# tricorder-photodiode-breakout-mk-1_1.net
KiCad netlist of a schematic drawn in EAGLE
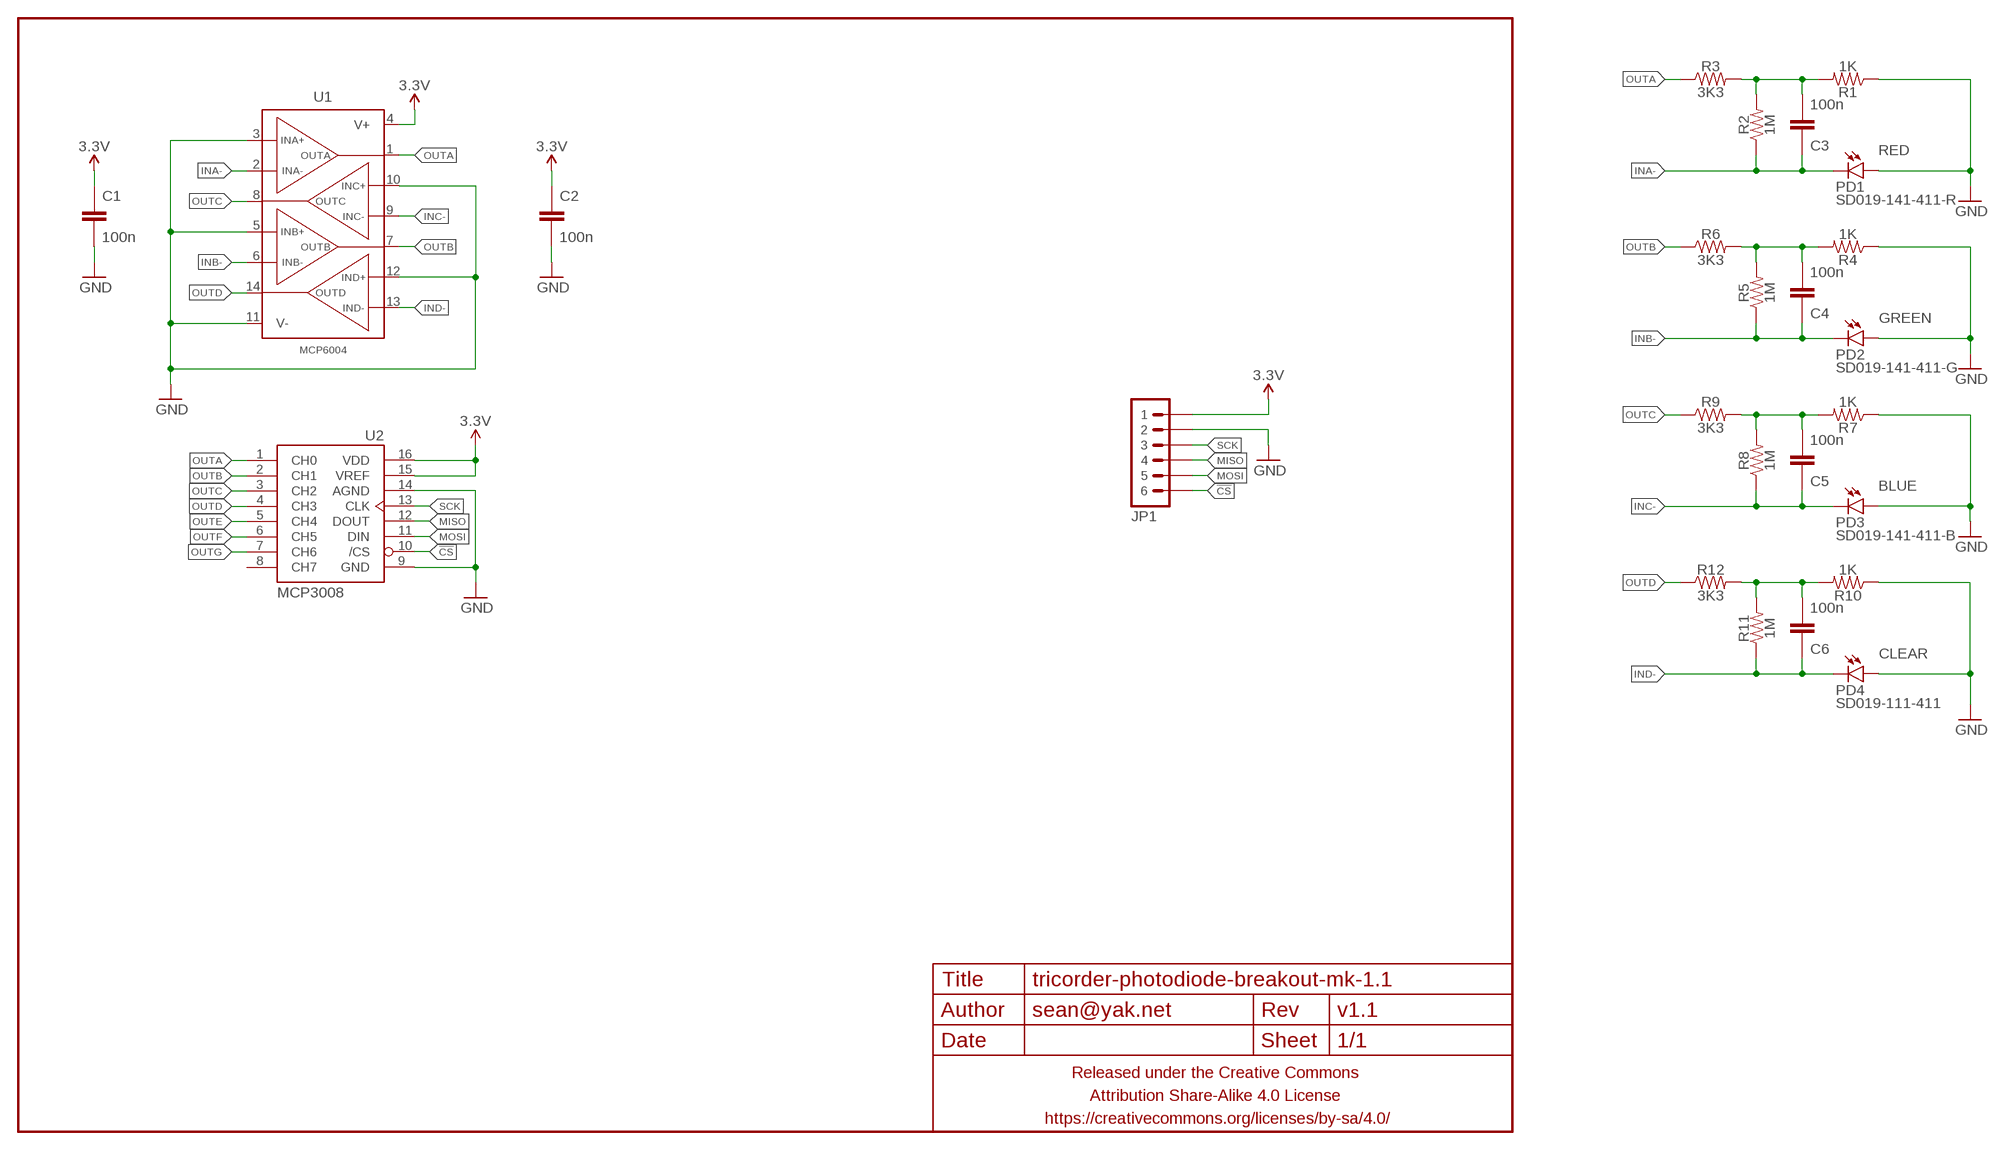
[diagram p0: schematic, sheet 1]

(export (version "E")
  (design (tool "Eeschema 10.0.6"))
  (components
    (comp (ref "C1")
      (value "100n")
      (footprint "eagle-import:C0603")
      (libsource (lib "eagle-import") (part "CAPACITOR-CERAMICC0603"))
    )
    (comp (ref "C2")
      (value "100n")
      (footprint "eagle-import:C0603")
      (libsource (lib "eagle-import") (part "CAPACITOR-CERAMICC0603"))
    )
    (comp (ref "C3")
      (value "100n")
      (footprint "eagle-import:C0603")
      (libsource (lib "eagle-import") (part "CAPACITOR-CERAMICC0603"))
    )
    (comp (ref "C4")
      (value "100n")
      (footprint "eagle-import:C0603")
      (libsource (lib "eagle-import") (part "CAPACITOR-CERAMICC0603"))
    )
    (comp (ref "C5")
      (value "100n")
      (footprint "eagle-import:C0603")
      (libsource (lib "eagle-import") (part "CAPACITOR-CERAMICC0603"))
    )
    (comp (ref "C6")
      (value "100n")
      (footprint "eagle-import:C0603")
      (libsource (lib "eagle-import") (part "CAPACITOR-CERAMICC0603"))
    )
    (comp (ref "FRAME1")
      (value "FRAME-LETTERNO_PACKAGE")
      (footprint "eagle-import:DUMMY")
      (fields (field (name "DESIGNER") "sean@yak.net") (field (name "VERSION") "v1.1"))
      (libsource (lib "eagle-import") (part "FRAME-LETTERNO_PACKAGE"))
    )
    (comp (ref "JP1")
      (value "M06JST-PH-PTH-VERT")
      (footprint "eagle-import:JST-6-PH-VERT-PTH")
      (libsource (lib "eagle-import") (part "M06JST-PH-PTH-VERT"))
    )
    (comp (ref "PD1")
      (value "SD019-141-411-R")
      (footprint "eagle-import:LED-0805")
      (libsource (lib "eagle-import") (part "PHOTODIODESMD-0805"))
    )
    (comp (ref "PD2")
      (value "SD019-141-411-G")
      (footprint "eagle-import:LED-0805")
      (libsource (lib "eagle-import") (part "PHOTODIODESMD-0805"))
    )
    (comp (ref "PD3")
      (value "SD019-141-411-B")
      (footprint "eagle-import:LED-0805")
      (libsource (lib "eagle-import") (part "PHOTODIODESMD-0805"))
    )
    (comp (ref "PD4")
      (value "SD019-111-411")
      (footprint "eagle-import:LED-0805")
      (libsource (lib "eagle-import") (part "PHOTODIODESMD-0805"))
    )
    (comp (ref "R1")
      (value "1K")
      (footprint "eagle-import:R0603")
      (libsource (lib "eagle-import") (part "RESISTORR0603"))
    )
    (comp (ref "R2")
      (value "1M")
      (footprint "eagle-import:R0603")
      (libsource (lib "eagle-import") (part "RESISTORR0603"))
    )
    (comp (ref "R3")
      (value "3K3")
      (footprint "eagle-import:R0603")
      (libsource (lib "eagle-import") (part "RESISTORR0603"))
    )
    (comp (ref "R4")
      (value "1K")
      (footprint "eagle-import:R0603")
      (libsource (lib "eagle-import") (part "RESISTORR0603"))
    )
    (comp (ref "R5")
      (value "1M")
      (footprint "eagle-import:R0603")
      (libsource (lib "eagle-import") (part "RESISTORR0603"))
    )
    (comp (ref "R6")
      (value "3K3")
      (footprint "eagle-import:R0603")
      (libsource (lib "eagle-import") (part "RESISTORR0603"))
    )
    (comp (ref "R7")
      (value "1K")
      (footprint "eagle-import:R0603")
      (libsource (lib "eagle-import") (part "RESISTORR0603"))
    )
    (comp (ref "R8")
      (value "1M")
      (footprint "eagle-import:R0603")
      (libsource (lib "eagle-import") (part "RESISTORR0603"))
    )
    (comp (ref "R9")
      (value "3K3")
      (footprint "eagle-import:R0603")
      (libsource (lib "eagle-import") (part "RESISTORR0603"))
    )
    (comp (ref "R10")
      (value "1K")
      (footprint "eagle-import:R0603")
      (libsource (lib "eagle-import") (part "RESISTORR0603"))
    )
    (comp (ref "R11")
      (value "1M")
      (footprint "eagle-import:R0603")
      (libsource (lib "eagle-import") (part "RESISTORR0603"))
    )
    (comp (ref "R12")
      (value "3K3")
      (footprint "eagle-import:R0603")
      (libsource (lib "eagle-import") (part "RESISTORR0603"))
    )
    (comp (ref "U1")
      (value "MCP6004")
      (footprint "eagle-import:SO14")
      (libsource (lib "eagle-import") (part "MCP6004SOIC14"))
    )
    (comp (ref "U2")
      (value "MCP3008")
      (footprint "eagle-import:SO16")
      (libsource (lib "eagle-import") (part "MCP3008SOIC16"))
    )
  )
  (nets
    (net (code "1") (name "/~{CS}") (class "Default")
      (node (ref "JP1") (pin "6") (pinfunction "6_6") (pintype "passive"))
      (node (ref "U2") (pin "10") (pinfunction "/CS_10") (pintype "input"))
    )
    (net (code "2") (name "3.3V") (class "Default")
      (node (ref "C1") (pin "1") (pinfunction "1_1") (pintype "passive"))
      (node (ref "C2") (pin "1") (pinfunction "1_1") (pintype "passive"))
      (node (ref "JP1") (pin "1") (pinfunction "1_1") (pintype "passive"))
      (node (ref "U1") (pin "4") (pinfunction "V+_4") (pintype "power_in"))
      (node (ref "U2") (pin "15") (pinfunction "VREF_15") (pintype "input"))
      (node (ref "U2") (pin "16") (pinfunction "VDD_16") (pintype "power_in"))
    )
    (net (code "3") (name "GND") (class "Default")
      (node (ref "C1") (pin "2") (pinfunction "2_2") (pintype "passive"))
      (node (ref "C2") (pin "2") (pinfunction "2_2") (pintype "passive"))
      (node (ref "JP1") (pin "2") (pinfunction "2_2") (pintype "passive"))
      (node (ref "PD1") (pin "A") (pinfunction "A_A") (pintype "passive"))
      (node (ref "PD2") (pin "A") (pinfunction "A_A") (pintype "passive"))
      (node (ref "PD3") (pin "A") (pinfunction "A_A") (pintype "passive"))
      (node (ref "PD4") (pin "A") (pinfunction "A_A") (pintype "passive"))
      (node (ref "R1") (pin "1") (pinfunction "1_1") (pintype "passive"))
      (node (ref "R10") (pin "1") (pinfunction "1_1") (pintype "passive"))
      (node (ref "R4") (pin "1") (pinfunction "1_1") (pintype "passive"))
      (node (ref "R7") (pin "1") (pinfunction "1_1") (pintype "passive"))
      (node (ref "U1") (pin "10") (pinfunction "INC+_10") (pintype "input"))
      (node (ref "U1") (pin "11") (pinfunction "V-_11") (pintype "power_in"))
      (node (ref "U1") (pin "12") (pinfunction "IND+_12") (pintype "input"))
      (node (ref "U1") (pin "3") (pinfunction "INA+_3") (pintype "input"))
      (node (ref "U1") (pin "5") (pinfunction "INB+_5") (pintype "input"))
      (node (ref "U2") (pin "14") (pinfunction "AGND_14") (pintype "power_in"))
      (node (ref "U2") (pin "9") (pinfunction "GND_9") (pintype "power_in"))
    )
    (net (code "4") (name "INA-") (class "Default")
      (node (ref "C3") (pin "1") (pinfunction "1_1") (pintype "passive"))
      (node (ref "PD1") (pin "C") (pinfunction "C_C") (pintype "passive"))
      (node (ref "R2") (pin "1") (pinfunction "1_1") (pintype "passive"))
      (node (ref "U1") (pin "2") (pinfunction "INA-_2") (pintype "input"))
    )
    (net (code "5") (name "INB-") (class "Default")
      (node (ref "C4") (pin "1") (pinfunction "1_1") (pintype "passive"))
      (node (ref "PD2") (pin "C") (pinfunction "C_C") (pintype "passive"))
      (node (ref "R5") (pin "1") (pinfunction "1_1") (pintype "passive"))
      (node (ref "U1") (pin "6") (pinfunction "INB-_6") (pintype "input"))
    )
    (net (code "6") (name "INC-") (class "Default")
      (node (ref "C5") (pin "1") (pinfunction "1_1") (pintype "passive"))
      (node (ref "PD3") (pin "C") (pinfunction "C_C") (pintype "passive"))
      (node (ref "R8") (pin "1") (pinfunction "1_1") (pintype "passive"))
      (node (ref "U1") (pin "9") (pinfunction "INC-_9") (pintype "input"))
    )
    (net (code "7") (name "IND-") (class "Default")
      (node (ref "C6") (pin "1") (pinfunction "1_1") (pintype "passive"))
      (node (ref "PD4") (pin "C") (pinfunction "C_C") (pintype "passive"))
      (node (ref "R11") (pin "1") (pinfunction "1_1") (pintype "passive"))
      (node (ref "U1") (pin "13") (pinfunction "IND-_13") (pintype "input"))
    )
    (net (code "8") (name "MISO") (class "Default")
      (node (ref "JP1") (pin "4") (pinfunction "4_4") (pintype "passive"))
      (node (ref "U2") (pin "12") (pinfunction "DOUT_12") (pintype "output"))
    )
    (net (code "9") (name "MOSI") (class "Default")
      (node (ref "JP1") (pin "5") (pinfunction "5_5") (pintype "passive"))
      (node (ref "U2") (pin "11") (pinfunction "DIN_11") (pintype "input"))
    )
    (net (code "10") (name "Net-(C3-Pad2)") (class "Default")
      (node (ref "C3") (pin "2") (pinfunction "2_2") (pintype "passive"))
      (node (ref "R1") (pin "2") (pinfunction "2_2") (pintype "passive"))
      (node (ref "R2") (pin "2") (pinfunction "2_2") (pintype "passive"))
      (node (ref "R3") (pin "2") (pinfunction "2_2") (pintype "passive"))
    )
    (net (code "11") (name "Net-(C4-Pad2)") (class "Default")
      (node (ref "C4") (pin "2") (pinfunction "2_2") (pintype "passive"))
      (node (ref "R4") (pin "2") (pinfunction "2_2") (pintype "passive"))
      (node (ref "R5") (pin "2") (pinfunction "2_2") (pintype "passive"))
      (node (ref "R6") (pin "2") (pinfunction "2_2") (pintype "passive"))
    )
    (net (code "12") (name "Net-(C5-Pad2)") (class "Default")
      (node (ref "C5") (pin "2") (pinfunction "2_2") (pintype "passive"))
      (node (ref "R7") (pin "2") (pinfunction "2_2") (pintype "passive"))
      (node (ref "R8") (pin "2") (pinfunction "2_2") (pintype "passive"))
      (node (ref "R9") (pin "2") (pinfunction "2_2") (pintype "passive"))
    )
    (net (code "13") (name "Net-(C6-Pad2)") (class "Default")
      (node (ref "C6") (pin "2") (pinfunction "2_2") (pintype "passive"))
      (node (ref "R10") (pin "2") (pinfunction "2_2") (pintype "passive"))
      (node (ref "R11") (pin "2") (pinfunction "2_2") (pintype "passive"))
      (node (ref "R12") (pin "2") (pinfunction "2_2") (pintype "passive"))
    )
    (net (code "14") (name "OUTA") (class "Default")
      (node (ref "R3") (pin "1") (pinfunction "1_1") (pintype "passive"))
      (node (ref "U1") (pin "1") (pinfunction "OUTA_1") (pintype "output"))
      (node (ref "U2") (pin "1") (pinfunction "CH0_1") (pintype "input"))
    )
    (net (code "15") (name "OUTB") (class "Default")
      (node (ref "R6") (pin "1") (pinfunction "1_1") (pintype "passive"))
      (node (ref "U1") (pin "7") (pinfunction "OUTB_7") (pintype "output"))
      (node (ref "U2") (pin "2") (pinfunction "CH1_2") (pintype "input"))
    )
    (net (code "16") (name "OUTC") (class "Default")
      (node (ref "R9") (pin "1") (pinfunction "1_1") (pintype "passive"))
      (node (ref "U1") (pin "8") (pinfunction "OUTC_8") (pintype "output"))
      (node (ref "U2") (pin "3") (pinfunction "CH2_3") (pintype "input"))
    )
    (net (code "17") (name "OUTD") (class "Default")
      (node (ref "R12") (pin "1") (pinfunction "1_1") (pintype "passive"))
      (node (ref "U1") (pin "14") (pinfunction "OUTD_14") (pintype "output"))
      (node (ref "U2") (pin "4") (pinfunction "CH3_4") (pintype "input"))
    )
    (net (code "18") (name "OUTE") (class "Default")
      (node (ref "U2") (pin "5") (pinfunction "CH4_5") (pintype "input"))
    )
    (net (code "19") (name "OUTF") (class "Default")
      (node (ref "U2") (pin "6") (pinfunction "CH5_6") (pintype "input"))
    )
    (net (code "20") (name "OUTG") (class "Default")
      (node (ref "U2") (pin "7") (pinfunction "CH6_7") (pintype "input"))
    )
    (net (code "21") (name "SCK") (class "Default")
      (node (ref "JP1") (pin "3") (pinfunction "3_3") (pintype "passive"))
      (node (ref "U2") (pin "13") (pinfunction "CLK_13") (pintype "input"))
    )
    (net (code "22") (name "unconnected-(U2-CH7-Pad8)") (class "Default")
      (node (ref "U2") (pin "8") (pinfunction "CH7_8") (pintype "input"))
    )
  )
)
